# SerialOLED.net
KiCad netlist of a schematic drawn in EAGLE
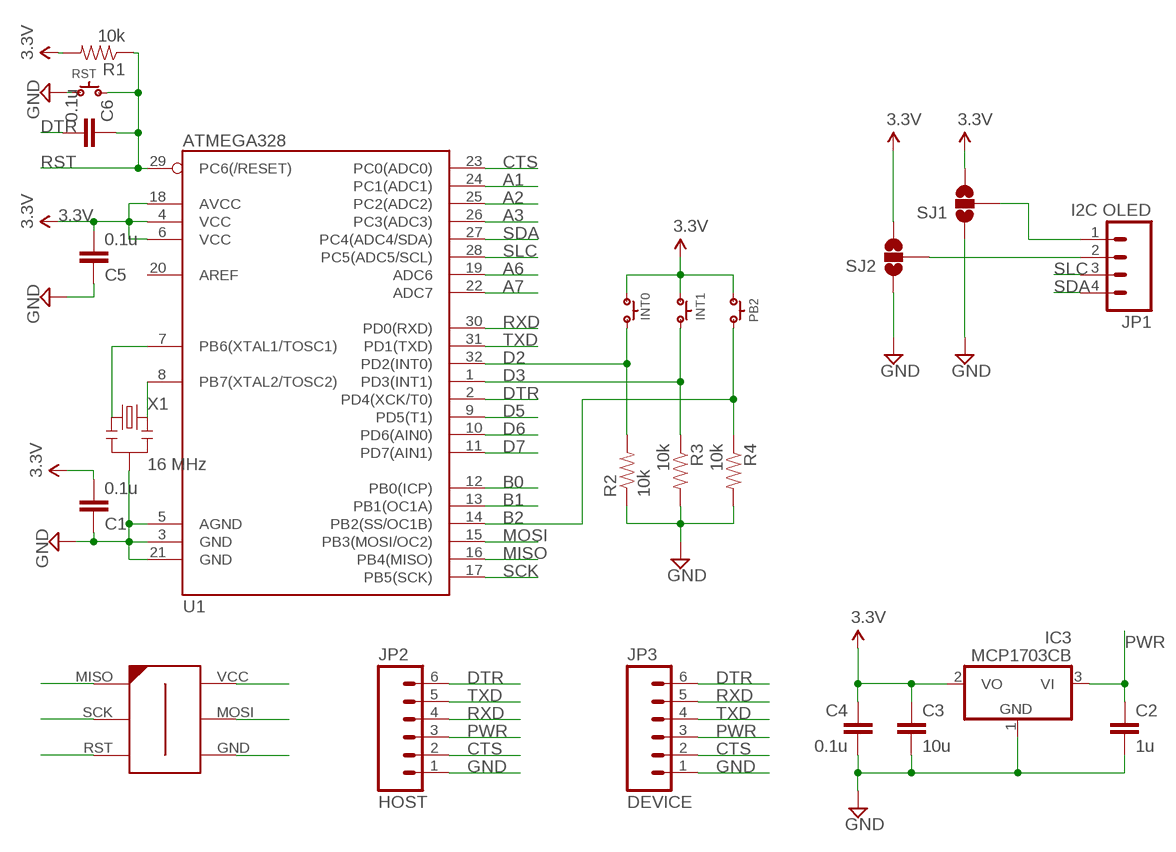
[diagram p0: schematic, sheet 1]

(export (version "E")
  (design (tool "Eeschema 10.0.6"))
  (components
    (comp (ref "C1")
      (value "0.1u")
      (footprint "eagle-import:0603-CAP")
      (libsource (lib "eagle-import") (part "CAP0603-CAP"))
    )
    (comp (ref "C2")
      (value "1u")
      (footprint "eagle-import:0603-CAP")
      (libsource (lib "eagle-import") (part "CAP0603-CAP"))
    )
    (comp (ref "C3")
      (value "10u")
      (footprint "eagle-import:0805")
      (libsource (lib "eagle-import") (part "CAP0805"))
    )
    (comp (ref "C4")
      (value "0.1u")
      (footprint "eagle-import:0603-CAP")
      (libsource (lib "eagle-import") (part "CAP0603-CAP"))
    )
    (comp (ref "C5")
      (value "0.1u")
      (footprint "eagle-import:0603-CAP")
      (libsource (lib "eagle-import") (part "CAP0603-CAP"))
    )
    (comp (ref "C6")
      (value "0.1u")
      (footprint "eagle-import:0603-CAP")
      (libsource (lib "eagle-import") (part "CAP0603-CAP"))
    )
    (comp (ref "IC3")
      (value "MCP1703CB")
      (footprint "eagle-import:SOT23")
      (libsource (lib "eagle-import") (part "MCP1703CB"))
    )
    (comp (ref "INT0")
      (value "SPST.B3U-3000P(M)-B")
      (footprint "eagle-import:B3U-3000P(M)-B")
      (libsource (lib "eagle-import") (part "SPST.B3U-3000P(M)-B"))
    )
    (comp (ref "INT1")
      (value "SPST.B3U-3000P(M)-B")
      (footprint "eagle-import:B3U-3000P(M)-B")
      (libsource (lib "eagle-import") (part "SPST.B3U-3000P(M)-B"))
    )
    (comp (ref "JP1")
      (value "I2C OLED")
      (footprint "eagle-import:1X04_LOCK")
      (libsource (lib "eagle-import") (part "M04LOCK"))
    )
    (comp (ref "JP2")
      (value "HOST")
      (footprint "eagle-import:1X06-SIP_LOCK")
      (libsource (lib "eagle-import") (part "M06SIP_LOCK"))
    )
    (comp (ref "JP3")
      (value "DEVICE")
      (footprint "eagle-import:1X06-SIP_LOCK")
      (libsource (lib "eagle-import") (part "M06SIP_LOCK"))
    )
    (comp (ref "PB2")
      (value "SPST.B3U-3000P(M)-B")
      (footprint "eagle-import:B3U-3000P(M)-B")
      (libsource (lib "eagle-import") (part "SPST.B3U-3000P(M)-B"))
    )
    (comp (ref "R1")
      (value "10k")
      (footprint "eagle-import:0603-RES")
      (libsource (lib "eagle-import") (part "RESISTOR0603-RES"))
    )
    (comp (ref "R2")
      (value "10k")
      (footprint "eagle-import:0603-RES")
      (libsource (lib "eagle-import") (part "RESISTOR0603-RES"))
    )
    (comp (ref "R3")
      (value "10k")
      (footprint "eagle-import:0603-RES")
      (libsource (lib "eagle-import") (part "RESISTOR0603-RES"))
    )
    (comp (ref "R4")
      (value "10k")
      (footprint "eagle-import:0603-RES")
      (libsource (lib "eagle-import") (part "RESISTOR0603-RES"))
    )
    (comp (ref "RST")
      (value "SPST.B3U-3000P(M)-B")
      (footprint "eagle-import:B3U-3000P(M)-B")
      (libsource (lib "eagle-import") (part "SPST.B3U-3000P(M)-B"))
    )
    (comp (ref "SJ1")
      (value "SOLDERJUMPER_2WAYPASTE1&2")
      (footprint "eagle-import:SJ_3_PASTE1&2")
      (libsource (lib "eagle-import") (part "SOLDERJUMPER_2WAYPASTE1&2"))
    )
    (comp (ref "SJ2")
      (value "SOLDERJUMPER_2WAYPASTE2&3")
      (footprint "eagle-import:SJ_3_PASTE2&3")
      (libsource (lib "eagle-import") (part "SOLDERJUMPER_2WAYPASTE2&3"))
    )
    (comp (ref "U$6")
      (value "AVR-ISP-6-EDGE")
      (footprint "eagle-import:6PAD_ISP")
      (libsource (lib "eagle-import") (part "AVR-ISP-6-EDGE"))
    )
    (comp (ref "U1")
      (value "ATMEGA328")
      (footprint "eagle-import:TQFP32-08")
      (libsource (lib "eagle-import") (part "ATMEGA168"))
    )
    (comp (ref "X1")
      (value "16 MHz")
      (footprint "eagle-import:RESONATOR-SMD")
      (libsource (lib "eagle-import") (part "RESONATORSMD"))
    )
  )
  (nets
    (net (code "1") (name "/A1") (class "Default")
      (node (ref "U1") (pin "24") (pinfunction "PC1(ADC1)_24") (pintype "bidirectional"))
    )
    (net (code "2") (name "/A2") (class "Default")
      (node (ref "U1") (pin "25") (pinfunction "PC2(ADC2)_25") (pintype "bidirectional"))
    )
    (net (code "3") (name "/A3") (class "Default")
      (node (ref "U1") (pin "26") (pinfunction "PC3(ADC3)_26") (pintype "bidirectional"))
    )
    (net (code "4") (name "/A6") (class "Default")
      (node (ref "U1") (pin "19") (pinfunction "ADC6_19") (pintype "bidirectional"))
    )
    (net (code "5") (name "/A7") (class "Default")
      (node (ref "U1") (pin "22") (pinfunction "ADC7_22") (pintype "bidirectional"))
    )
    (net (code "6") (name "/B0") (class "Default")
      (node (ref "U1") (pin "12") (pinfunction "PB0(ICP)_12") (pintype "bidirectional"))
    )
    (net (code "7") (name "/B1") (class "Default")
      (node (ref "U1") (pin "13") (pinfunction "PB1(OC1A)_13") (pintype "bidirectional"))
    )
    (net (code "8") (name "/B2") (class "Default")
      (node (ref "PB2") (pin "2") (pinfunction "2_2") (pintype "bidirectional"))
      (node (ref "R4") (pin "1") (pinfunction "1_1") (pintype "passive"))
      (node (ref "U1") (pin "14") (pinfunction "PB2(SS/OC1B)_14") (pintype "bidirectional"))
    )
    (net (code "9") (name "/CTS") (class "Default")
      (node (ref "JP2") (pin "2") (pinfunction "2_2") (pintype "passive"))
      (node (ref "JP3") (pin "2") (pinfunction "2_2") (pintype "passive"))
      (node (ref "U1") (pin "23") (pinfunction "PC0(ADC0)_23") (pintype "bidirectional"))
    )
    (net (code "10") (name "/D2") (class "Default")
      (node (ref "INT0") (pin "2") (pinfunction "2_2") (pintype "bidirectional"))
      (node (ref "R2") (pin "2") (pinfunction "2_2") (pintype "passive"))
      (node (ref "U1") (pin "32") (pinfunction "PD2(INT0)_32") (pintype "bidirectional"))
    )
    (net (code "11") (name "/D3") (class "Default")
      (node (ref "INT1") (pin "1") (pinfunction "1_1") (pintype "bidirectional"))
      (node (ref "R3") (pin "1") (pinfunction "1_1") (pintype "passive"))
      (node (ref "U1") (pin "1") (pinfunction "PD3(INT1)_1") (pintype "bidirectional"))
    )
    (net (code "12") (name "/D5") (class "Default")
      (node (ref "U1") (pin "9") (pinfunction "PD5(T1)_9") (pintype "bidirectional"))
    )
    (net (code "13") (name "/D6") (class "Default")
      (node (ref "U1") (pin "10") (pinfunction "PD6(AIN0)_10") (pintype "bidirectional"))
    )
    (net (code "14") (name "/D7") (class "Default")
      (node (ref "U1") (pin "11") (pinfunction "PD7(AIN1)_11") (pintype "bidirectional"))
    )
    (net (code "15") (name "/DTR") (class "Default")
      (node (ref "C6") (pin "2") (pinfunction "2_2") (pintype "passive"))
      (node (ref "JP2") (pin "6") (pinfunction "6_6") (pintype "passive"))
      (node (ref "JP3") (pin "6") (pinfunction "6_6") (pintype "passive"))
      (node (ref "U1") (pin "2") (pinfunction "PD4(XCK/T0)_2") (pintype "bidirectional"))
    )
    (net (code "16") (name "/MISO") (class "Default")
      (node (ref "U$6") (pin "MISO") (pinfunction "P$1_MISO") (pintype "bidirectional"))
      (node (ref "U1") (pin "16") (pinfunction "PB4(MISO)_16") (pintype "bidirectional"))
    )
    (net (code "17") (name "/MOSI") (class "Default")
      (node (ref "U$6") (pin "MOSI") (pinfunction "P$5_MOSI") (pintype "bidirectional"))
      (node (ref "U1") (pin "15") (pinfunction "PB3(MOSI/OC2)_15") (pintype "bidirectional"))
    )
    (net (code "18") (name "/PWR") (class "Default")
      (node (ref "C2") (pin "1") (pinfunction "1_1") (pintype "passive"))
      (node (ref "IC3") (pin "3") (pinfunction "VI_3") (pintype "input"))
      (node (ref "JP2") (pin "3") (pinfunction "3_3") (pintype "passive"))
      (node (ref "JP3") (pin "3") (pinfunction "3_3") (pintype "passive"))
    )
    (net (code "19") (name "/RST") (class "Default")
      (node (ref "C6") (pin "1") (pinfunction "1_1") (pintype "passive"))
      (node (ref "R1") (pin "1") (pinfunction "1_1") (pintype "passive"))
      (node (ref "RST") (pin "2") (pinfunction "2_2") (pintype "bidirectional"))
      (node (ref "U$6") (pin "RST") (pinfunction "P$3_RST") (pintype "bidirectional"))
      (node (ref "U1") (pin "29") (pinfunction "PC6(/RESET)_29") (pintype "bidirectional"))
    )
    (net (code "20") (name "/RXD") (class "Default")
      (node (ref "JP2") (pin "4") (pinfunction "4_4") (pintype "passive"))
      (node (ref "JP3") (pin "5") (pinfunction "5_5") (pintype "passive"))
      (node (ref "U1") (pin "30") (pinfunction "PD0(RXD)_30") (pintype "bidirectional"))
    )
    (net (code "21") (name "/SCK") (class "Default")
      (node (ref "U$6") (pin "SCK") (pinfunction "P$2_SCK") (pintype "bidirectional"))
      (node (ref "U1") (pin "17") (pinfunction "PB5(SCK)_17") (pintype "bidirectional"))
    )
    (net (code "22") (name "/SDA") (class "Default")
      (node (ref "JP1") (pin "4") (pinfunction "4_4") (pintype "passive"))
      (node (ref "U1") (pin "27") (pinfunction "PC4(ADC4/SDA)_27") (pintype "bidirectional"))
    )
    (net (code "23") (name "/SLC") (class "Default")
      (node (ref "JP1") (pin "3") (pinfunction "3_3") (pintype "passive"))
      (node (ref "U1") (pin "28") (pinfunction "PC5(ADC5/SCL)_28") (pintype "bidirectional"))
    )
    (net (code "24") (name "/TXD") (class "Default")
      (node (ref "JP2") (pin "5") (pinfunction "5_5") (pintype "passive"))
      (node (ref "JP3") (pin "4") (pinfunction "4_4") (pintype "passive"))
      (node (ref "U1") (pin "31") (pinfunction "PD1(TXD)_31") (pintype "bidirectional"))
    )
    (net (code "25") (name "3.3V") (class "Default")
      (node (ref "C1") (pin "2") (pinfunction "2_2") (pintype "passive"))
      (node (ref "C3") (pin "1") (pinfunction "1_1") (pintype "passive"))
      (node (ref "C4") (pin "1") (pinfunction "1_1") (pintype "passive"))
      (node (ref "C5") (pin "2") (pinfunction "2_2") (pintype "passive"))
      (node (ref "IC3") (pin "2") (pinfunction "VO_2") (pintype "passive"))
      (node (ref "INT0") (pin "1") (pinfunction "1_1") (pintype "bidirectional"))
      (node (ref "INT1") (pin "2") (pinfunction "2_2") (pintype "bidirectional"))
      (node (ref "PB2") (pin "1") (pinfunction "1_1") (pintype "bidirectional"))
      (node (ref "R1") (pin "2") (pinfunction "2_2") (pintype "passive"))
      (node (ref "SJ1") (pin "3") (pinfunction "3_3") (pintype "passive"))
      (node (ref "SJ2") (pin "3") (pinfunction "3_3") (pintype "passive"))
      (node (ref "U$6") (pin "VCC") (pinfunction "P$6_VCC") (pintype "bidirectional"))
      (node (ref "U1") (pin "18") (pinfunction "AVCC_18") (pintype "bidirectional"))
      (node (ref "U1") (pin "4") (pinfunction "VCC_4") (pintype "bidirectional"))
      (node (ref "U1") (pin "6") (pinfunction "VCC_6") (pintype "bidirectional"))
    )
    (net (code "26") (name "GND") (class "Default")
      (node (ref "C1") (pin "1") (pinfunction "1_1") (pintype "passive"))
      (node (ref "C2") (pin "2") (pinfunction "2_2") (pintype "passive"))
      (node (ref "C3") (pin "2") (pinfunction "2_2") (pintype "passive"))
      (node (ref "C4") (pin "2") (pinfunction "2_2") (pintype "passive"))
      (node (ref "C5") (pin "1") (pinfunction "1_1") (pintype "passive"))
      (node (ref "IC3") (pin "1") (pinfunction "GND_1") (pintype "passive"))
      (node (ref "JP2") (pin "1") (pinfunction "1_1") (pintype "passive"))
      (node (ref "JP3") (pin "1") (pinfunction "1_1") (pintype "passive"))
      (node (ref "R2") (pin "1") (pinfunction "1_1") (pintype "passive"))
      (node (ref "R3") (pin "2") (pinfunction "2_2") (pintype "passive"))
      (node (ref "R4") (pin "2") (pinfunction "2_2") (pintype "passive"))
      (node (ref "RST") (pin "1") (pinfunction "1_1") (pintype "bidirectional"))
      (node (ref "SJ1") (pin "1") (pinfunction "1_1") (pintype "passive"))
      (node (ref "SJ2") (pin "1") (pinfunction "1_1") (pintype "passive"))
      (node (ref "U$6") (pin "GND") (pinfunction "P$4_GND") (pintype "bidirectional"))
      (node (ref "U1") (pin "21") (pinfunction "GND_21") (pintype "bidirectional"))
      (node (ref "U1") (pin "3") (pinfunction "GND_3") (pintype "bidirectional"))
      (node (ref "U1") (pin "5") (pinfunction "AGND_5") (pintype "bidirectional"))
      (node (ref "X1") (pin "2") (pinfunction "2_2") (pintype "passive"))
    )
    (net (code "27") (name "Net-(JP1-Pad1)") (class "Default")
      (node (ref "JP1") (pin "1") (pinfunction "1_1") (pintype "passive"))
      (node (ref "SJ1") (pin "2") (pinfunction "2_2") (pintype "passive"))
    )
    (net (code "28") (name "Net-(JP1-Pad2)") (class "Default")
      (node (ref "JP1") (pin "2") (pinfunction "2_2") (pintype "passive"))
      (node (ref "SJ2") (pin "2") (pinfunction "2_2") (pintype "passive"))
    )
    (net (code "29") (name "Net-(U1-PB6(XTAL1{slash}TOSC1))") (class "Default")
      (node (ref "U1") (pin "7") (pinfunction "PB6(XTAL1/TOSC1)_7") (pintype "bidirectional"))
      (node (ref "X1") (pin "1") (pinfunction "1_1") (pintype "passive"))
    )
    (net (code "30") (name "Net-(U1-PB7(XTAL2{slash}TOSC2))") (class "Default")
      (node (ref "U1") (pin "8") (pinfunction "PB7(XTAL2/TOSC2)_8") (pintype "bidirectional"))
      (node (ref "X1") (pin "3") (pinfunction "3_3") (pintype "passive"))
    )
    (net (code "31") (name "unconnected-(U1-AREF-Pad20)") (class "Default")
      (node (ref "U1") (pin "20") (pinfunction "AREF_20") (pintype "bidirectional"))
    )
  )
)
